# led_analog_watch_mvmt_v1_3.net
KiCad netlist of a schematic drawn in EAGLE
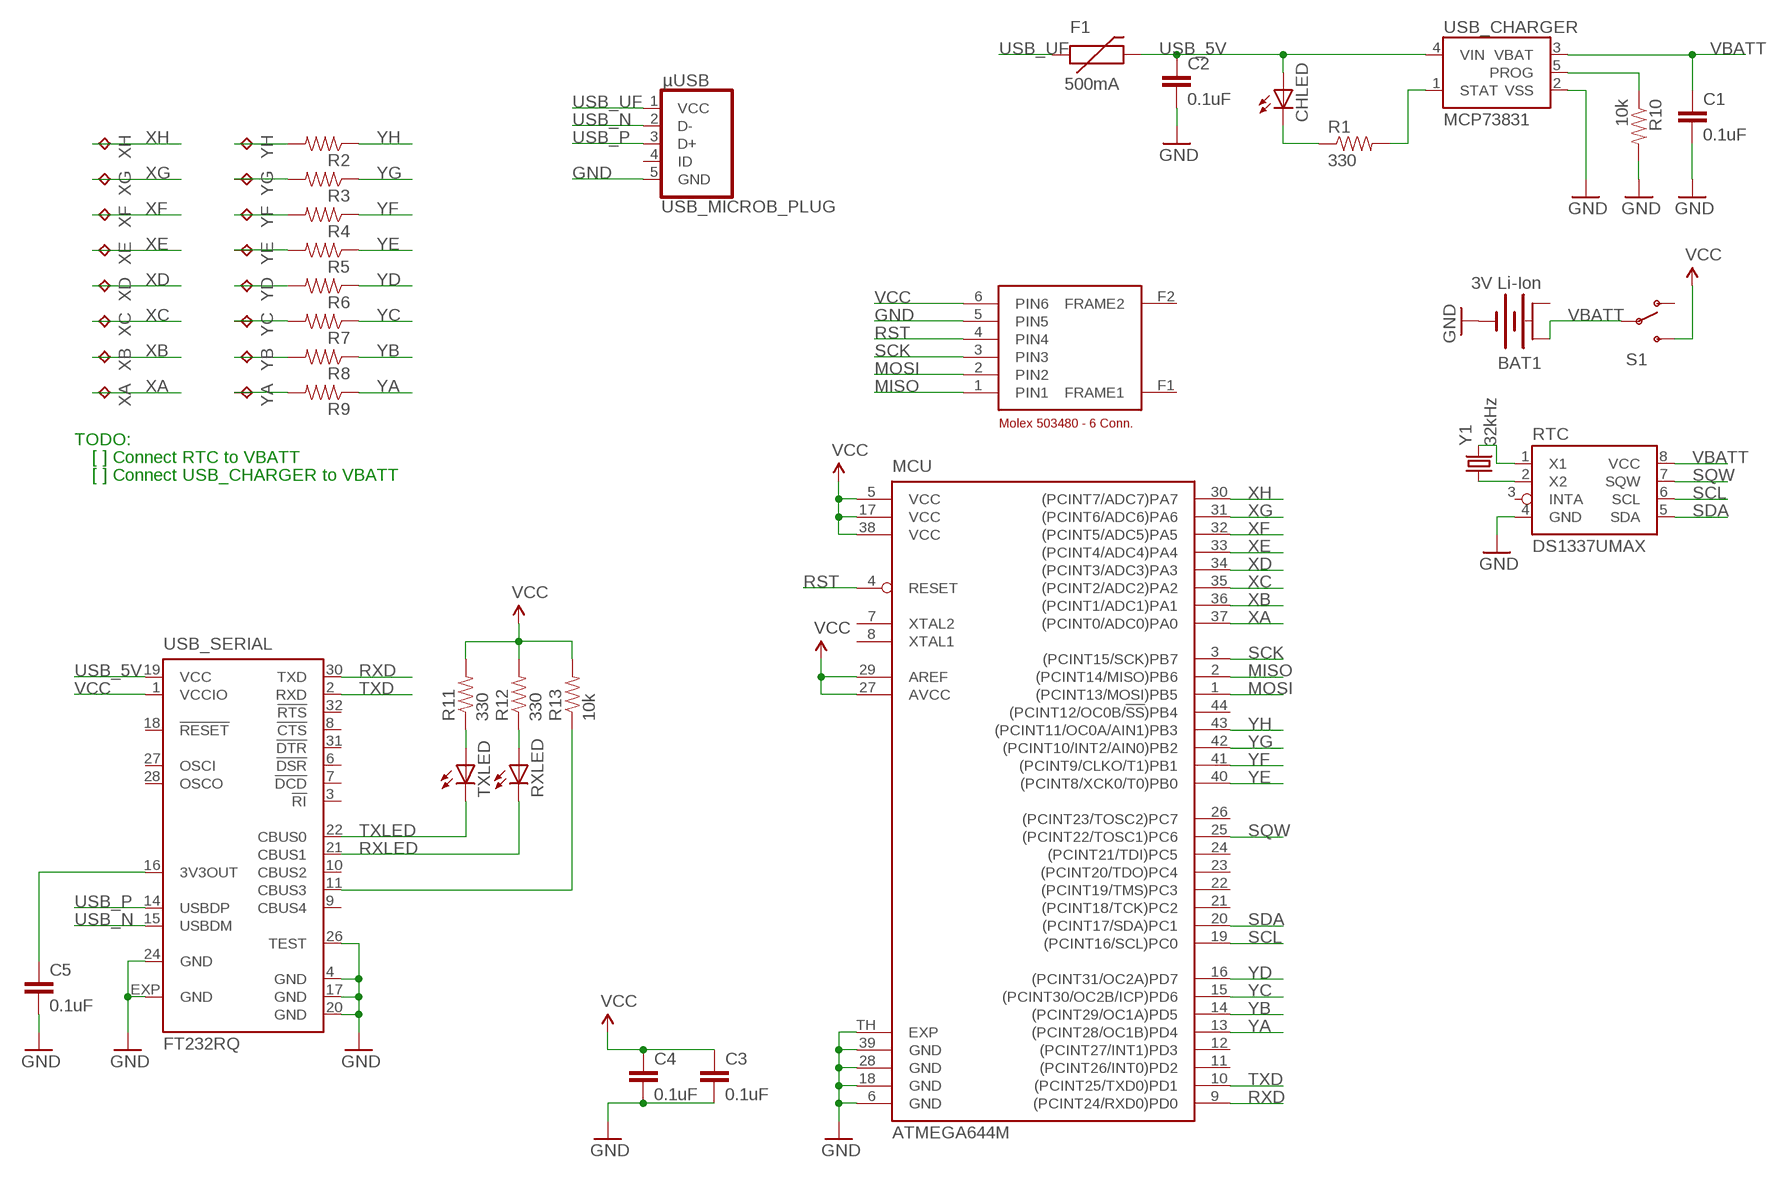
[diagram p0: schematic, sheet 1]

(export (version "E")
  (design (tool "Eeschema 10.0.6"))
  (components
    (comp (ref "BAT1")
      (value "3V Li-Ion")
      (footprint "eagle-import:BATTCON_245MM_PTH")
      (libsource (lib "eagle-import") (part "BATTERY245PTH"))
    )
    (comp (ref "C1")
      (value "0.1uF")
      (footprint "eagle-import:0603-CAP")
      (libsource (lib "eagle-import") (part "CAP-0603"))
    )
    (comp (ref "C2")
      (value "0.1uF")
      (footprint "eagle-import:0603-CAP")
      (libsource (lib "eagle-import") (part "CAP-0603"))
    )
    (comp (ref "C3")
      (value "0.1uF")
      (footprint "eagle-import:0603-CAP")
      (libsource (lib "eagle-import") (part "CAP-0603"))
    )
    (comp (ref "C4")
      (value "0.1uF")
      (footprint "eagle-import:0603-CAP")
      (libsource (lib "eagle-import") (part "CAP-0603"))
    )
    (comp (ref "C5")
      (value "0.1uF")
      (footprint "eagle-import:0603-CAP")
      (libsource (lib "eagle-import") (part "CAP-0603"))
    )
    (comp (ref "CHLED")
      (value "LED-0402")
      (footprint "eagle-import:0402")
      (libsource (lib "eagle-import") (part "LED-0402"))
    )
    (comp (ref "F1")
      (value "500mA")
      (footprint "eagle-import:0603")
      (libsource (lib "eagle-import") (part "PTC0603"))
    )
    (comp (ref "MCU")
      (value "ATMEGA644M")
      (footprint "eagle-import:MLF44-TH")
      (fields (field (name "MPN") "ATMEGA644P-20MU"))
      (libsource (lib "eagle-import") (part "ATMEGA644M"))
    )
    (comp (ref "R1")
      (value "330")
      (footprint "eagle-import:0603")
      (libsource (lib "eagle-import") (part "RESISTOR-0603"))
    )
    (comp (ref "R2")
      (value "RESISTOR-0603")
      (footprint "eagle-import:0603")
      (libsource (lib "eagle-import") (part "RESISTOR-0603"))
    )
    (comp (ref "R3")
      (value "RESISTOR-0603")
      (footprint "eagle-import:0603")
      (libsource (lib "eagle-import") (part "RESISTOR-0603"))
    )
    (comp (ref "R4")
      (value "RESISTOR-0603")
      (footprint "eagle-import:0603")
      (libsource (lib "eagle-import") (part "RESISTOR-0603"))
    )
    (comp (ref "R5")
      (value "RESISTOR-0603")
      (footprint "eagle-import:0603")
      (libsource (lib "eagle-import") (part "RESISTOR-0603"))
    )
    (comp (ref "R6")
      (value "RESISTOR-0603")
      (footprint "eagle-import:0603")
      (libsource (lib "eagle-import") (part "RESISTOR-0603"))
    )
    (comp (ref "R7")
      (value "RESISTOR-0603")
      (footprint "eagle-import:0603")
      (libsource (lib "eagle-import") (part "RESISTOR-0603"))
    )
    (comp (ref "R8")
      (value "RESISTOR-0603")
      (footprint "eagle-import:0603")
      (libsource (lib "eagle-import") (part "RESISTOR-0603"))
    )
    (comp (ref "R9")
      (value "RESISTOR-0603")
      (footprint "eagle-import:0603")
      (libsource (lib "eagle-import") (part "RESISTOR-0603"))
    )
    (comp (ref "R10")
      (value "10k")
      (footprint "eagle-import:0603")
      (libsource (lib "eagle-import") (part "RESISTOR-0603"))
    )
    (comp (ref "R11")
      (value "330")
      (footprint "eagle-import:0603")
      (libsource (lib "eagle-import") (part "RESISTOR-0603"))
    )
    (comp (ref "R12")
      (value "330")
      (footprint "eagle-import:0603")
      (libsource (lib "eagle-import") (part "RESISTOR-0603"))
    )
    (comp (ref "R13")
      (value "10k")
      (footprint "eagle-import:0603")
      (libsource (lib "eagle-import") (part "RESISTOR-0603"))
    )
    (comp (ref "RTC")
      (value "DS1337UMAX")
      (footprint "eagle-import:UMAX8")
      (libsource (lib "eagle-import") (part "DS1337UMAX"))
    )
    (comp (ref "RXLED")
      (value "LED-0402")
      (footprint "eagle-import:0402")
      (libsource (lib "eagle-import") (part "LED-0402"))
    )
    (comp (ref "S1")
      (value "SWITCH-SPSTMA12R")
      (footprint "eagle-import:SWITCH-MA12R")
      (libsource (lib "eagle-import") (part "SWITCH-SPSTMA12R"))
    )
    (comp (ref "TXLED")
      (value "LED-0402")
      (footprint "eagle-import:0402")
      (libsource (lib "eagle-import") (part "LED-0402"))
    )
    (comp (ref "U$2")
      (value "MOLEX_503480")
      (footprint "eagle-import:MOLEX_503480")
      (libsource (lib "eagle-import") (part "MOLEX_503480"))
    )
    (comp (ref "USB_CHARGER")
      (value "MCP73831")
      (footprint "eagle-import:SOT23-5")
      (libsource (lib "eagle-import") (part "MCP73831"))
    )
    (comp (ref "USB_SERIAL")
      (value "FT232RQ")
      (footprint "eagle-import:QFN32")
      (libsource (lib "eagle-import") (part "FT232RQ"))
    )
    (comp (ref "XA")
      (value "TPTP20R")
      (footprint "eagle-import:TP20R")
      (libsource (lib "eagle-import") (part "TPTP20R"))
    )
    (comp (ref "XB")
      (value "TPTP20R")
      (footprint "eagle-import:TP20R")
      (libsource (lib "eagle-import") (part "TPTP20R"))
    )
    (comp (ref "XC")
      (value "TPTP20R")
      (footprint "eagle-import:TP20R")
      (libsource (lib "eagle-import") (part "TPTP20R"))
    )
    (comp (ref "XD")
      (value "TPTP20R")
      (footprint "eagle-import:TP20R")
      (libsource (lib "eagle-import") (part "TPTP20R"))
    )
    (comp (ref "XE")
      (value "TPTP20R")
      (footprint "eagle-import:TP20R")
      (libsource (lib "eagle-import") (part "TPTP20R"))
    )
    (comp (ref "XF")
      (value "TPTP20R")
      (footprint "eagle-import:TP20R")
      (libsource (lib "eagle-import") (part "TPTP20R"))
    )
    (comp (ref "XG")
      (value "TPTP20R")
      (footprint "eagle-import:TP20R")
      (libsource (lib "eagle-import") (part "TPTP20R"))
    )
    (comp (ref "XH")
      (value "TPTP20R")
      (footprint "eagle-import:TP20R")
      (libsource (lib "eagle-import") (part "TPTP20R"))
    )
    (comp (ref "Y1")
      (value "32kHz")
      (footprint "eagle-import:CRYSTAL-ABS10-SMD")
      (libsource (lib "eagle-import") (part "CRYSTALABS10"))
    )
    (comp (ref "YA")
      (value "TPTP20R")
      (footprint "eagle-import:TP20R")
      (libsource (lib "eagle-import") (part "TPTP20R"))
    )
    (comp (ref "YB")
      (value "TPTP20R")
      (footprint "eagle-import:TP20R")
      (libsource (lib "eagle-import") (part "TPTP20R"))
    )
    (comp (ref "YC")
      (value "TPTP20R")
      (footprint "eagle-import:TP20R")
      (libsource (lib "eagle-import") (part "TPTP20R"))
    )
    (comp (ref "YD")
      (value "TPTP20R")
      (footprint "eagle-import:TP20R")
      (libsource (lib "eagle-import") (part "TPTP20R"))
    )
    (comp (ref "YE")
      (value "TPTP20R")
      (footprint "eagle-import:TP20R")
      (libsource (lib "eagle-import") (part "TPTP20R"))
    )
    (comp (ref "YF")
      (value "TPTP20R")
      (footprint "eagle-import:TP20R")
      (libsource (lib "eagle-import") (part "TPTP20R"))
    )
    (comp (ref "YG")
      (value "TPTP20R")
      (footprint "eagle-import:TP20R")
      (libsource (lib "eagle-import") (part "TPTP20R"))
    )
    (comp (ref "YH")
      (value "TPTP20R")
      (footprint "eagle-import:TP20R")
      (libsource (lib "eagle-import") (part "TPTP20R"))
    )
    (comp (ref "µUSB")
      (value "USB_MICROB_PLUG")
      (footprint "eagle-import:USB_MICRO_B_TYCO")
      (libsource (lib "eagle-import") (part "USB_MICROB_PLUG"))
    )
  )
  (nets
    (net (code "1") (name "/+B") (class "Default")
      (node (ref "BAT1") (pin "1") (pinfunction "+B_1") (pintype "power_in"))
    )
    (net (code "2") (name "/MISO") (class "Default")
      (node (ref "MCU") (pin "2") (pinfunction "(PCINT14/MISO)PB6_2") (pintype "bidirectional"))
      (node (ref "U$2") (pin "1") (pinfunction "PIN1_1") (pintype "bidirectional"))
    )
    (net (code "3") (name "/MOSI") (class "Default")
      (node (ref "MCU") (pin "1") (pinfunction "(PCINT13/MOSI)PB5_1") (pintype "bidirectional"))
      (node (ref "U$2") (pin "2") (pinfunction "PIN2_2") (pintype "bidirectional"))
    )
    (net (code "4") (name "/RST") (class "Default")
      (node (ref "MCU") (pin "4") (pinfunction "RESET_4") (pintype "input"))
      (node (ref "U$2") (pin "4") (pinfunction "PIN4_4") (pintype "bidirectional"))
    )
    (net (code "5") (name "/RXD") (class "Default")
      (node (ref "MCU") (pin "9") (pinfunction "(PCINT24/RXD0)PD0_9") (pintype "bidirectional"))
      (node (ref "USB_SERIAL") (pin "30") (pinfunction "TXD_30") (pintype "output"))
    )
    (net (code "6") (name "/RXLED") (class "Default")
      (node (ref "RXLED") (pin "2") (pinfunction "C_2") (pintype "passive"))
      (node (ref "USB_SERIAL") (pin "21") (pinfunction "CBUS1_21") (pintype "bidirectional"))
    )
    (net (code "7") (name "/SCK") (class "Default")
      (node (ref "MCU") (pin "3") (pinfunction "(PCINT15/SCK)PB7_3") (pintype "bidirectional"))
      (node (ref "U$2") (pin "3") (pinfunction "PIN3_3") (pintype "bidirectional"))
    )
    (net (code "8") (name "/SCL") (class "Default")
      (node (ref "MCU") (pin "19") (pinfunction "(PCINT16/SCL)PC0_19") (pintype "output"))
      (node (ref "RTC") (pin "6") (pinfunction "SCL_6") (pintype "bidirectional"))
    )
    (net (code "9") (name "/SDA") (class "Default")
      (node (ref "MCU") (pin "20") (pinfunction "(PCINT17/SDA)PC1_20") (pintype "output"))
      (node (ref "RTC") (pin "5") (pinfunction "SDA_5") (pintype "bidirectional"))
    )
    (net (code "10") (name "/SQW") (class "Default")
      (node (ref "MCU") (pin "25") (pinfunction "(PCINT22/TOSC1)PC6_25") (pintype "output"))
      (node (ref "RTC") (pin "7") (pinfunction "SQW_7") (pintype "bidirectional"))
    )
    (net (code "11") (name "/TXD") (class "Default")
      (node (ref "MCU") (pin "10") (pinfunction "(PCINT25/TXD0)PD1_10") (pintype "bidirectional"))
      (node (ref "USB_SERIAL") (pin "2") (pinfunction "RXD_2") (pintype "input"))
    )
    (net (code "12") (name "/TXLED") (class "Default")
      (node (ref "TXLED") (pin "2") (pinfunction "C_2") (pintype "passive"))
      (node (ref "USB_SERIAL") (pin "22") (pinfunction "CBUS0_22") (pintype "bidirectional"))
    )
    (net (code "13") (name "/USB_5V") (class "Default")
      (node (ref "C2") (pin "1") (pinfunction "1_1") (pintype "passive"))
      (node (ref "CHLED") (pin "1") (pinfunction "A_1") (pintype "passive"))
      (node (ref "F1") (pin "2") (pinfunction "2_2") (pintype "bidirectional"))
      (node (ref "USB_CHARGER") (pin "4") (pinfunction "VIN_4") (pintype "power_in"))
      (node (ref "USB_SERIAL") (pin "19") (pinfunction "VCC_19") (pintype "power_in"))
    )
    (net (code "14") (name "/USB_N") (class "Default")
      (node (ref "USB_SERIAL") (pin "15") (pinfunction "USBDM_15") (pintype "bidirectional"))
      (node (ref "µUSB") (pin "2") (pinfunction "D-_2") (pintype "bidirectional"))
    )
    (net (code "15") (name "/USB_P") (class "Default")
      (node (ref "USB_SERIAL") (pin "14") (pinfunction "USBDP_14") (pintype "bidirectional"))
      (node (ref "µUSB") (pin "3") (pinfunction "D+_3") (pintype "bidirectional"))
    )
    (net (code "16") (name "/USB_UF") (class "Default")
      (node (ref "F1") (pin "1") (pinfunction "1_1") (pintype "bidirectional"))
      (node (ref "µUSB") (pin "1") (pinfunction "VCC_1") (pintype "bidirectional"))
    )
    (net (code "17") (name "/VBATT") (class "Default")
      (node (ref "BAT1") (pin "3") (pinfunction "+A_3") (pintype "power_in"))
      (node (ref "C1") (pin "1") (pinfunction "1_1") (pintype "passive"))
      (node (ref "RTC") (pin "8") (pinfunction "VCC_8") (pintype "bidirectional"))
      (node (ref "S1") (pin "2") (pinfunction "P_2") (pintype "passive"))
      (node (ref "USB_CHARGER") (pin "3") (pinfunction "VBAT_3") (pintype "power_in"))
    )
    (net (code "18") (name "/XA") (class "Default")
      (node (ref "MCU") (pin "37") (pinfunction "(PCINT0/ADC0)PA0_37") (pintype "bidirectional"))
      (node (ref "XA") (pin "TP") (pinfunction "TP_TP") (pintype "input"))
    )
    (net (code "19") (name "/XB") (class "Default")
      (node (ref "MCU") (pin "36") (pinfunction "(PCINT1/ADC1)PA1_36") (pintype "bidirectional"))
      (node (ref "XB") (pin "TP") (pinfunction "TP_TP") (pintype "input"))
    )
    (net (code "20") (name "/XC") (class "Default")
      (node (ref "MCU") (pin "35") (pinfunction "(PCINT2/ADC2)PA2_35") (pintype "bidirectional"))
      (node (ref "XC") (pin "TP") (pinfunction "TP_TP") (pintype "input"))
    )
    (net (code "21") (name "/XD") (class "Default")
      (node (ref "MCU") (pin "34") (pinfunction "(PCINT3/ADC3)PA3_34") (pintype "bidirectional"))
      (node (ref "XD") (pin "TP") (pinfunction "TP_TP") (pintype "input"))
    )
    (net (code "22") (name "/XE") (class "Default")
      (node (ref "MCU") (pin "33") (pinfunction "(PCINT4/ADC4)PA4_33") (pintype "bidirectional"))
      (node (ref "XE") (pin "TP") (pinfunction "TP_TP") (pintype "input"))
    )
    (net (code "23") (name "/XF") (class "Default")
      (node (ref "MCU") (pin "32") (pinfunction "(PCINT5/ADC5)PA5_32") (pintype "bidirectional"))
      (node (ref "XF") (pin "TP") (pinfunction "TP_TP") (pintype "input"))
    )
    (net (code "24") (name "/XG") (class "Default")
      (node (ref "MCU") (pin "31") (pinfunction "(PCINT6/ADC6)PA6_31") (pintype "bidirectional"))
      (node (ref "XG") (pin "TP") (pinfunction "TP_TP") (pintype "input"))
    )
    (net (code "25") (name "/XH") (class "Default")
      (node (ref "MCU") (pin "30") (pinfunction "(PCINT7/ADC7)PA7_30") (pintype "bidirectional"))
      (node (ref "XH") (pin "TP") (pinfunction "TP_TP") (pintype "input"))
    )
    (net (code "26") (name "/YA") (class "Default")
      (node (ref "MCU") (pin "13") (pinfunction "(PCINT28/OC1B)PD4_13") (pintype "bidirectional"))
      (node (ref "R9") (pin "1") (pinfunction "1_1") (pintype "passive"))
    )
    (net (code "27") (name "/YB") (class "Default")
      (node (ref "MCU") (pin "14") (pinfunction "(PCINT29/OC1A)PD5_14") (pintype "bidirectional"))
      (node (ref "R8") (pin "1") (pinfunction "1_1") (pintype "passive"))
    )
    (net (code "28") (name "/YC") (class "Default")
      (node (ref "MCU") (pin "15") (pinfunction "(PCINT30/OC2B/ICP)PD6_15") (pintype "bidirectional"))
      (node (ref "R7") (pin "1") (pinfunction "1_1") (pintype "passive"))
    )
    (net (code "29") (name "/YD") (class "Default")
      (node (ref "MCU") (pin "16") (pinfunction "(PCINT31/OC2A)PD7_16") (pintype "bidirectional"))
      (node (ref "R6") (pin "1") (pinfunction "1_1") (pintype "passive"))
    )
    (net (code "30") (name "/YE") (class "Default")
      (node (ref "MCU") (pin "40") (pinfunction "(PCINT8/XCK0/T0)PB0_40") (pintype "bidirectional"))
      (node (ref "R5") (pin "1") (pinfunction "1_1") (pintype "passive"))
    )
    (net (code "31") (name "/YF") (class "Default")
      (node (ref "MCU") (pin "41") (pinfunction "(PCINT9/CLKO/T1)PB1_41") (pintype "bidirectional"))
      (node (ref "R4") (pin "1") (pinfunction "1_1") (pintype "passive"))
    )
    (net (code "32") (name "/YG") (class "Default")
      (node (ref "MCU") (pin "42") (pinfunction "(PCINT10/INT2/AIN0)PB2_42") (pintype "bidirectional"))
      (node (ref "R3") (pin "1") (pinfunction "1_1") (pintype "passive"))
    )
    (net (code "33") (name "/YH") (class "Default")
      (node (ref "MCU") (pin "43") (pinfunction "(PCINT11/OC0A/AIN1)PB3_43") (pintype "bidirectional"))
      (node (ref "R2") (pin "1") (pinfunction "1_1") (pintype "passive"))
    )
    (net (code "34") (name "GND") (class "Default")
      (node (ref "BAT1") (pin "2") (pinfunction "-_2") (pintype "power_in"))
      (node (ref "C1") (pin "2") (pinfunction "2_2") (pintype "passive"))
      (node (ref "C2") (pin "2") (pinfunction "2_2") (pintype "passive"))
      (node (ref "C3") (pin "2") (pinfunction "2_2") (pintype "passive"))
      (node (ref "C4") (pin "2") (pinfunction "2_2") (pintype "passive"))
      (node (ref "C5") (pin "2") (pinfunction "2_2") (pintype "passive"))
      (node (ref "MCU") (pin "18") (pinfunction "GND_18") (pintype "power_in"))
      (node (ref "MCU") (pin "28") (pinfunction "GND_28") (pintype "power_in"))
      (node (ref "MCU") (pin "39") (pinfunction "GND_39") (pintype "power_in"))
      (node (ref "MCU") (pin "6") (pinfunction "GND_6") (pintype "power_in"))
      (node (ref "MCU") (pin "TH") (pinfunction "EXP_TH") (pintype "power_in"))
      (node (ref "R10") (pin "2") (pinfunction "2_2") (pintype "passive"))
      (node (ref "RTC") (pin "4") (pinfunction "GND_4") (pintype "bidirectional"))
      (node (ref "U$2") (pin "5") (pinfunction "PIN5_5") (pintype "bidirectional"))
      (node (ref "USB_CHARGER") (pin "2") (pinfunction "VSS_2") (pintype "power_in"))
      (node (ref "USB_SERIAL") (pin "17") (pinfunction "GND_17") (pintype "power_in"))
      (node (ref "USB_SERIAL") (pin "20") (pinfunction "GND_20") (pintype "power_in"))
      (node (ref "USB_SERIAL") (pin "24") (pinfunction "GND_24") (pintype "power_in"))
      (node (ref "USB_SERIAL") (pin "26") (pinfunction "TEST_26") (pintype "input"))
      (node (ref "USB_SERIAL") (pin "4") (pinfunction "GND_4") (pintype "power_in"))
      (node (ref "USB_SERIAL") (pin "EXP") (pinfunction "GND_EXP") (pintype "power_in"))
      (node (ref "µUSB") (pin "5") (pinfunction "GND_5") (pintype "bidirectional"))
    )
    (net (code "35") (name "Net-(CHLED-C)") (class "Default")
      (node (ref "CHLED") (pin "2") (pinfunction "C_2") (pintype "passive"))
      (node (ref "R1") (pin "1") (pinfunction "1_1") (pintype "passive"))
    )
    (net (code "36") (name "Net-(R2-Pad2)") (class "Default")
      (node (ref "R2") (pin "2") (pinfunction "2_2") (pintype "passive"))
      (node (ref "YH") (pin "TP") (pinfunction "TP_TP") (pintype "input"))
    )
    (net (code "37") (name "Net-(R3-Pad2)") (class "Default")
      (node (ref "R3") (pin "2") (pinfunction "2_2") (pintype "passive"))
      (node (ref "YG") (pin "TP") (pinfunction "TP_TP") (pintype "input"))
    )
    (net (code "38") (name "Net-(R4-Pad2)") (class "Default")
      (node (ref "R4") (pin "2") (pinfunction "2_2") (pintype "passive"))
      (node (ref "YF") (pin "TP") (pinfunction "TP_TP") (pintype "input"))
    )
    (net (code "39") (name "Net-(R5-Pad2)") (class "Default")
      (node (ref "R5") (pin "2") (pinfunction "2_2") (pintype "passive"))
      (node (ref "YE") (pin "TP") (pinfunction "TP_TP") (pintype "input"))
    )
    (net (code "40") (name "Net-(R6-Pad2)") (class "Default")
      (node (ref "R6") (pin "2") (pinfunction "2_2") (pintype "passive"))
      (node (ref "YD") (pin "TP") (pinfunction "TP_TP") (pintype "input"))
    )
    (net (code "41") (name "Net-(R7-Pad2)") (class "Default")
      (node (ref "R7") (pin "2") (pinfunction "2_2") (pintype "passive"))
      (node (ref "YC") (pin "TP") (pinfunction "TP_TP") (pintype "input"))
    )
    (net (code "42") (name "Net-(R8-Pad2)") (class "Default")
      (node (ref "R8") (pin "2") (pinfunction "2_2") (pintype "passive"))
      (node (ref "YB") (pin "TP") (pinfunction "TP_TP") (pintype "input"))
    )
    (net (code "43") (name "Net-(R9-Pad2)") (class "Default")
      (node (ref "R9") (pin "2") (pinfunction "2_2") (pintype "passive"))
      (node (ref "YA") (pin "TP") (pinfunction "TP_TP") (pintype "input"))
    )
    (net (code "44") (name "Net-(RTC-X1)") (class "Default")
      (node (ref "RTC") (pin "1") (pinfunction "X1_1") (pintype "bidirectional"))
      (node (ref "Y1") (pin "X2") (pinfunction "2_X2") (pintype "passive"))
    )
    (net (code "45") (name "Net-(RTC-X2)") (class "Default")
      (node (ref "RTC") (pin "2") (pinfunction "X2_2") (pintype "bidirectional"))
      (node (ref "Y1") (pin "X1") (pinfunction "1_X1") (pintype "passive"))
    )
    (net (code "46") (name "Net-(RXLED-A)") (class "Default")
      (node (ref "R12") (pin "1") (pinfunction "1_1") (pintype "passive"))
      (node (ref "RXLED") (pin "1") (pinfunction "A_1") (pintype "passive"))
    )
    (net (code "47") (name "Net-(TXLED-A)") (class "Default")
      (node (ref "R11") (pin "1") (pinfunction "1_1") (pintype "passive"))
      (node (ref "TXLED") (pin "1") (pinfunction "A_1") (pintype "passive"))
    )
    (net (code "48") (name "Net-(USB_CHARGER-PROG)") (class "Default")
      (node (ref "R10") (pin "1") (pinfunction "1_1") (pintype "passive"))
      (node (ref "USB_CHARGER") (pin "5") (pinfunction "PROG_5") (pintype "input"))
    )
    (net (code "49") (name "Net-(USB_CHARGER-STAT)") (class "Default")
      (node (ref "R1") (pin "2") (pinfunction "2_2") (pintype "passive"))
      (node (ref "USB_CHARGER") (pin "1") (pinfunction "STAT_1") (pintype "output"))
    )
    (net (code "50") (name "Net-(USB_SERIAL-3V3OUT)") (class "Default")
      (node (ref "C5") (pin "1") (pinfunction "1_1") (pintype "passive"))
      (node (ref "USB_SERIAL") (pin "16") (pinfunction "3V3OUT_16") (pintype "output"))
    )
    (net (code "51") (name "Net-(USB_SERIAL-CBUS3)") (class "Default")
      (node (ref "R13") (pin "1") (pinfunction "1_1") (pintype "passive"))
      (node (ref "USB_SERIAL") (pin "11") (pinfunction "CBUS3_11") (pintype "bidirectional"))
    )
    (net (code "52") (name "VCC") (class "Default")
      (node (ref "C3") (pin "1") (pinfunction "1_1") (pintype "passive"))
      (node (ref "C4") (pin "1") (pinfunction "1_1") (pintype "passive"))
      (node (ref "MCU") (pin "17") (pinfunction "VCC_17") (pintype "power_in"))
      (node (ref "MCU") (pin "27") (pinfunction "AVCC_27") (pintype "power_in"))
      (node (ref "MCU") (pin "29") (pinfunction "AREF_29") (pintype "passive"))
      (node (ref "MCU") (pin "38") (pinfunction "VCC_38") (pintype "power_in"))
      (node (ref "MCU") (pin "5") (pinfunction "VCC_5") (pintype "power_in"))
      (node (ref "R11") (pin "2") (pinfunction "2_2") (pintype "passive"))
      (node (ref "R12") (pin "2") (pinfunction "2_2") (pintype "passive"))
      (node (ref "R13") (pin "2") (pinfunction "2_2") (pintype "passive"))
      (node (ref "S1") (pin "3") (pinfunction "S_3") (pintype "passive"))
      (node (ref "U$2") (pin "6") (pinfunction "PIN6_6") (pintype "bidirectional"))
      (node (ref "USB_SERIAL") (pin "1") (pinfunction "VCCIO_1") (pintype "power_in"))
    )
    (net (code "53") (name "unconnected-(MCU-(PCINT12{slash}OC0B{slash}~{SS})PB4-Pad44)") (class "Default")
      (node (ref "MCU") (pin "44") (pinfunction "(PCINT12/OC0B/~{SS})PB4_44") (pintype "bidirectional"))
    )
    (net (code "54") (name "unconnected-(MCU-(PCINT18{slash}TCK)PC2-Pad21)") (class "Default")
      (node (ref "MCU") (pin "21") (pinfunction "(PCINT18/TCK)PC2_21") (pintype "output"))
    )
    (net (code "55") (name "unconnected-(MCU-(PCINT19{slash}TMS)PC3-Pad22)") (class "Default")
      (node (ref "MCU") (pin "22") (pinfunction "(PCINT19/TMS)PC3_22") (pintype "output"))
    )
    (net (code "56") (name "unconnected-(MCU-(PCINT20{slash}TDO)PC4-Pad23)") (class "Default")
      (node (ref "MCU") (pin "23") (pinfunction "(PCINT20/TDO)PC4_23") (pintype "output"))
    )
    (net (code "57") (name "unconnected-(MCU-(PCINT21{slash}TDI)PC5-Pad24)") (class "Default")
      (node (ref "MCU") (pin "24") (pinfunction "(PCINT21/TDI)PC5_24") (pintype "output"))
    )
    (net (code "58") (name "unconnected-(MCU-(PCINT23{slash}TOSC2)PC7-Pad26)") (class "Default")
      (node (ref "MCU") (pin "26") (pinfunction "(PCINT23/TOSC2)PC7_26") (pintype "output"))
    )
    (net (code "59") (name "unconnected-(MCU-(PCINT26{slash}INT0)PD2-Pad11)") (class "Default")
      (node (ref "MCU") (pin "11") (pinfunction "(PCINT26/INT0)PD2_11") (pintype "bidirectional"))
    )
    (net (code "60") (name "unconnected-(MCU-(PCINT27{slash}INT1)PD3-Pad12)") (class "Default")
      (node (ref "MCU") (pin "12") (pinfunction "(PCINT27/INT1)PD3_12") (pintype "bidirectional"))
    )
    (net (code "61") (name "unconnected-(MCU-XTAL1-Pad8)") (class "Default")
      (node (ref "MCU") (pin "8") (pinfunction "XTAL1_8") (pintype "bidirectional"))
    )
    (net (code "62") (name "unconnected-(MCU-XTAL2-Pad7)") (class "Default")
      (node (ref "MCU") (pin "7") (pinfunction "XTAL2_7") (pintype "bidirectional"))
    )
    (net (code "63") (name "unconnected-(RTC-INTA-Pad3)") (class "Default")
      (node (ref "RTC") (pin "3") (pinfunction "INTA_3") (pintype "bidirectional"))
    )
    (net (code "64") (name "unconnected-(S1-O-Pad1)") (class "Default")
      (node (ref "S1") (pin "1") (pinfunction "O_1") (pintype "passive"))
    )
    (net (code "65") (name "unconnected-(U$2-FRAME1-PadF1)") (class "Default")
      (node (ref "U$2") (pin "F1") (pinfunction "FRAME1_F1") (pintype "bidirectional"))
    )
    (net (code "66") (name "unconnected-(U$2-FRAME2-PadF2)") (class "Default")
      (node (ref "U$2") (pin "F2") (pinfunction "FRAME2_F2") (pintype "bidirectional"))
    )
    (net (code "67") (name "unconnected-(USB_SERIAL-CBUS2-Pad10)") (class "Default")
      (node (ref "USB_SERIAL") (pin "10") (pinfunction "CBUS2_10") (pintype "bidirectional"))
    )
    (net (code "68") (name "unconnected-(USB_SERIAL-CBUS4-Pad9)") (class "Default")
      (node (ref "USB_SERIAL") (pin "9") (pinfunction "CBUS4_9") (pintype "bidirectional"))
    )
    (net (code "69") (name "unconnected-(USB_SERIAL-OSCI-Pad27)") (class "Default")
      (node (ref "USB_SERIAL") (pin "27") (pinfunction "OSCI_27") (pintype "input"))
    )
    (net (code "70") (name "unconnected-(USB_SERIAL-OSCO-Pad28)") (class "Default")
      (node (ref "USB_SERIAL") (pin "28") (pinfunction "OSCO_28") (pintype "output"))
    )
    (net (code "71") (name "unconnected-(USB_SERIAL-~{CTS}-Pad8)") (class "Default")
      (node (ref "USB_SERIAL") (pin "8") (pinfunction "~{CTS}_8") (pintype "input"))
    )
    (net (code "72") (name "unconnected-(USB_SERIAL-~{DCD}-Pad7)") (class "Default")
      (node (ref "USB_SERIAL") (pin "7") (pinfunction "~{DCD}_7") (pintype "input"))
    )
    (net (code "73") (name "unconnected-(USB_SERIAL-~{DSR}-Pad6)") (class "Default")
      (node (ref "USB_SERIAL") (pin "6") (pinfunction "~{DSR}_6") (pintype "input"))
    )
    (net (code "74") (name "unconnected-(USB_SERIAL-~{DTR}-Pad31)") (class "Default")
      (node (ref "USB_SERIAL") (pin "31") (pinfunction "~{DTR}_31") (pintype "output"))
    )
    (net (code "75") (name "unconnected-(USB_SERIAL-~{RESET}-Pad18)") (class "Default")
      (node (ref "USB_SERIAL") (pin "18") (pinfunction "~{RESET}_18") (pintype "input"))
    )
    (net (code "76") (name "unconnected-(USB_SERIAL-~{RI}-Pad3)") (class "Default")
      (node (ref "USB_SERIAL") (pin "3") (pinfunction "~{RI}_3") (pintype "input"))
    )
    (net (code "77") (name "unconnected-(USB_SERIAL-~{RTS}-Pad32)") (class "Default")
      (node (ref "USB_SERIAL") (pin "32") (pinfunction "~{RTS}_32") (pintype "output"))
    )
    (net (code "78") (name "unconnected-(µUSB-ID-Pad4)") (class "Default")
      (node (ref "µUSB") (pin "4") (pinfunction "ID_4") (pintype "bidirectional"))
    )
  )
)
